# frets.net
KiCad netlist of a schematic drawn in EAGLE
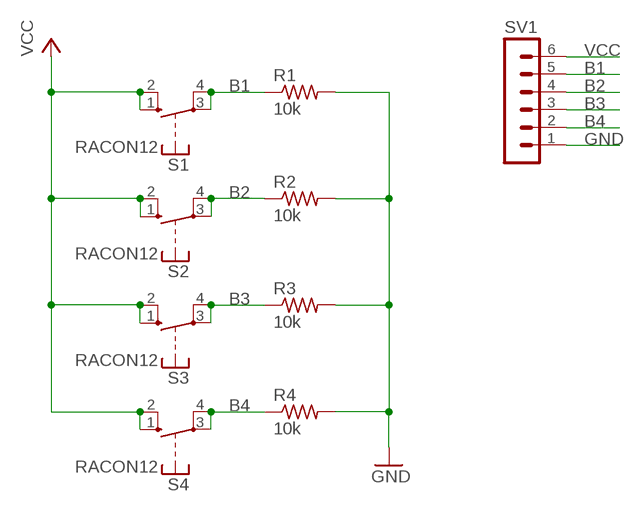
[diagram p0: schematic, sheet 1]

(export (version "E")
  (design (tool "Eeschema 10.0.6"))
  (components
    (comp (ref "R1")
      (value "10k")
      (footprint "eagle-import:0207_7")
      (libsource (lib "eagle-import") (part "R-US_0207/7"))
    )
    (comp (ref "R2")
      (value "10k")
      (footprint "eagle-import:0207_7")
      (libsource (lib "eagle-import") (part "R-US_0207/7"))
    )
    (comp (ref "R3")
      (value "10k")
      (footprint "eagle-import:0207_7")
      (libsource (lib "eagle-import") (part "R-US_0207/7"))
    )
    (comp (ref "R4")
      (value "10k")
      (footprint "eagle-import:0207_7")
      (libsource (lib "eagle-import") (part "R-US_0207/7"))
    )
    (comp (ref "S1")
      (value "RACON12")
      (footprint "eagle-import:RACON12")
      (libsource (lib "eagle-import") (part "RACON12"))
    )
    (comp (ref "S2")
      (value "RACON12")
      (footprint "eagle-import:RACON12")
      (libsource (lib "eagle-import") (part "RACON12"))
    )
    (comp (ref "S3")
      (value "RACON12")
      (footprint "eagle-import:RACON12")
      (libsource (lib "eagle-import") (part "RACON12"))
    )
    (comp (ref "S4")
      (value "RACON12")
      (footprint "eagle-import:RACON12")
      (libsource (lib "eagle-import") (part "RACON12"))
    )
    (comp (ref "SV1")
      (value "MA06-1")
      (footprint "eagle-import:MA06-1")
      (libsource (lib "eagle-import") (part "MA06-1"))
    )
  )
  (nets
    (net (code "1") (name "/B1") (class "Default")
      (node (ref "R1") (pin "1") (pinfunction "1_1") (pintype "passive"))
      (node (ref "S1") (pin "3") (pinfunction "P_3") (pintype "passive"))
      (node (ref "S1") (pin "4") (pinfunction "P_4") (pintype "passive"))
      (node (ref "SV1") (pin "5") (pinfunction "5_5") (pintype "passive"))
    )
    (net (code "2") (name "/B2") (class "Default")
      (node (ref "R2") (pin "1") (pinfunction "1_1") (pintype "passive"))
      (node (ref "S2") (pin "3") (pinfunction "P_3") (pintype "passive"))
      (node (ref "S2") (pin "4") (pinfunction "P_4") (pintype "passive"))
      (node (ref "SV1") (pin "4") (pinfunction "4_4") (pintype "passive"))
    )
    (net (code "3") (name "/B3") (class "Default")
      (node (ref "R3") (pin "1") (pinfunction "1_1") (pintype "passive"))
      (node (ref "S3") (pin "3") (pinfunction "P_3") (pintype "passive"))
      (node (ref "S3") (pin "4") (pinfunction "P_4") (pintype "passive"))
      (node (ref "SV1") (pin "3") (pinfunction "3_3") (pintype "passive"))
    )
    (net (code "4") (name "/B4") (class "Default")
      (node (ref "R4") (pin "1") (pinfunction "1_1") (pintype "passive"))
      (node (ref "S4") (pin "3") (pinfunction "P_3") (pintype "passive"))
      (node (ref "S4") (pin "4") (pinfunction "P_4") (pintype "passive"))
      (node (ref "SV1") (pin "2") (pinfunction "2_2") (pintype "passive"))
    )
    (net (code "5") (name "GND") (class "Default")
      (node (ref "R1") (pin "2") (pinfunction "2_2") (pintype "passive"))
      (node (ref "R2") (pin "2") (pinfunction "2_2") (pintype "passive"))
      (node (ref "R3") (pin "2") (pinfunction "2_2") (pintype "passive"))
      (node (ref "R4") (pin "2") (pinfunction "2_2") (pintype "passive"))
      (node (ref "SV1") (pin "1") (pinfunction "1_1") (pintype "passive"))
    )
    (net (code "6") (name "VCC") (class "Default")
      (node (ref "S1") (pin "1") (pinfunction "S_1") (pintype "passive"))
      (node (ref "S1") (pin "2") (pinfunction "S_2") (pintype "passive"))
      (node (ref "S2") (pin "1") (pinfunction "S_1") (pintype "passive"))
      (node (ref "S2") (pin "2") (pinfunction "S_2") (pintype "passive"))
      (node (ref "S3") (pin "1") (pinfunction "S_1") (pintype "passive"))
      (node (ref "S3") (pin "2") (pinfunction "S_2") (pintype "passive"))
      (node (ref "S4") (pin "1") (pinfunction "S_1") (pintype "passive"))
      (node (ref "S4") (pin "2") (pinfunction "S_2") (pintype "passive"))
      (node (ref "SV1") (pin "6") (pinfunction "6_6") (pintype "passive"))
    )
  )
)
